# AGG_OBD.net
KiCad netlist of a schematic drawn in EAGLE
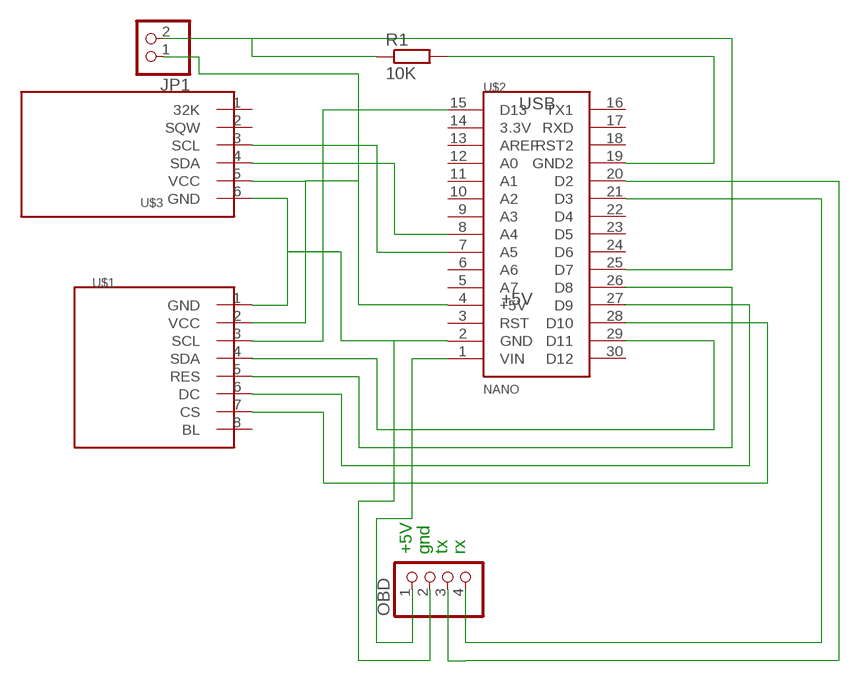
[diagram p0: schematic, sheet 1]

(export (version "E")
  (design (tool "Eeschema 10.0.6"))
  (components
    (comp (ref "JP1")
      (value "PINHD-1X2")
      (footprint "eagle-import:1X02")
      (libsource (lib "eagle-import") (part "PINHD-1X2"))
    )
    (comp (ref "OBD")
      (value "PINHD-1X4")
      (footprint "eagle-import:1X04")
      (libsource (lib "eagle-import") (part "PINHD-1X4"))
    )
    (comp (ref "R1")
      (value "10K")
      (footprint "eagle-import:0207_5V")
      (libsource (lib "eagle-import") (part "R-EU_0207/5V"))
    )
    (comp (ref "U$1")
      (value "DISPLAY_TFT_LCD_128X160")
      (footprint "eagle-import:DISPLAYTFT_LCD128X160")
      (libsource (lib "eagle-import") (part "DISPLAY_TFT_LCD_128X160"))
    )
    (comp (ref "U$2")
      (value "NANO")
      (footprint "eagle-import:NANO")
      (libsource (lib "eagle-import") (part "NANO"))
    )
    (comp (ref "U$3")
      (value "DS3231DS3231")
      (footprint "eagle-import:DS3231")
      (libsource (lib "eagle-import") (part "DS3231DS3231"))
    )
  )
  (nets
    (net (code "1") (name "Net-(U$1-CS)") (class "Default")
      (node (ref "U$1") (pin "7") (pinfunction "CS_7") (pintype "bidirectional"))
      (node (ref "U$2") (pin "28") (pinfunction "D10_28") (pintype "bidirectional"))
    )
    (net (code "2") (name "Net-(U$1-DC)") (class "Default")
      (node (ref "U$1") (pin "6") (pinfunction "DC_6") (pintype "bidirectional"))
      (node (ref "U$2") (pin "27") (pinfunction "D9_27") (pintype "bidirectional"))
    )
    (net (code "3") (name "Net-(U$1-GND)") (class "Default")
      (node (ref "OBD") (pin "2") (pinfunction "2_2") (pintype "passive"))
      (node (ref "U$1") (pin "1") (pinfunction "GND_1") (pintype "bidirectional"))
      (node (ref "U$2") (pin "2") (pinfunction "GND_2") (pintype "bidirectional"))
      (node (ref "U$3") (pin "6") (pinfunction "GND_6") (pintype "bidirectional"))
    )
    (net (code "4") (name "Net-(U$1-RES)") (class "Default")
      (node (ref "U$1") (pin "5") (pinfunction "RES_5") (pintype "bidirectional"))
      (node (ref "U$2") (pin "26") (pinfunction "D8_26") (pintype "bidirectional"))
    )
    (net (code "5") (name "Net-(U$1-SCL)") (class "Default")
      (node (ref "U$1") (pin "3") (pinfunction "SCL_3") (pintype "bidirectional"))
      (node (ref "U$2") (pin "15") (pinfunction "D13_15") (pintype "bidirectional"))
    )
    (net (code "6") (name "Net-(U$1-SDA)") (class "Default")
      (node (ref "U$1") (pin "4") (pinfunction "SDA_4") (pintype "bidirectional"))
      (node (ref "U$2") (pin "29") (pinfunction "D11_29") (pintype "bidirectional"))
    )
    (net (code "7") (name "Net-(U$1-VCC)") (class "Default")
      (node (ref "JP1") (pin "1") (pinfunction "1_1") (pintype "passive"))
      (node (ref "U$1") (pin "2") (pinfunction "VCC_2") (pintype "bidirectional"))
      (node (ref "U$2") (pin "4") (pinfunction "+5V_4") (pintype "bidirectional"))
      (node (ref "U$3") (pin "5") (pinfunction "VCC_5") (pintype "bidirectional"))
    )
    (net (code "8") (name "Net-(U$2-A4)") (class "Default")
      (node (ref "U$2") (pin "8") (pinfunction "A4_8") (pintype "bidirectional"))
      (node (ref "U$3") (pin "4") (pinfunction "SDA_4") (pintype "bidirectional"))
    )
    (net (code "9") (name "Net-(U$2-A5)") (class "Default")
      (node (ref "U$2") (pin "7") (pinfunction "A5_7") (pintype "bidirectional"))
      (node (ref "U$3") (pin "3") (pinfunction "SCL_3") (pintype "bidirectional"))
    )
    (net (code "10") (name "Net-(U$2-D2)") (class "Default")
      (node (ref "OBD") (pin "3") (pinfunction "3_3") (pintype "passive"))
      (node (ref "U$2") (pin "20") (pinfunction "D2_20") (pintype "bidirectional"))
    )
    (net (code "11") (name "Net-(U$2-D3)") (class "Default")
      (node (ref "OBD") (pin "4") (pinfunction "4_4") (pintype "passive"))
      (node (ref "U$2") (pin "21") (pinfunction "D3_21") (pintype "bidirectional"))
    )
    (net (code "12") (name "Net-(U$2-D7)") (class "Default")
      (node (ref "JP1") (pin "2") (pinfunction "2_2") (pintype "passive"))
      (node (ref "R1") (pin "1") (pinfunction "1_1") (pintype "passive"))
      (node (ref "U$2") (pin "25") (pinfunction "D7_25") (pintype "bidirectional"))
    )
    (net (code "13") (name "Net-(U$2-GND2)") (class "Default")
      (node (ref "R1") (pin "2") (pinfunction "2_2") (pintype "passive"))
      (node (ref "U$2") (pin "19") (pinfunction "GND2_19") (pintype "bidirectional"))
    )
    (net (code "14") (name "Net-(U$2-VIN)") (class "Default")
      (node (ref "OBD") (pin "1") (pinfunction "1_1") (pintype "passive"))
      (node (ref "U$2") (pin "1") (pinfunction "VIN_1") (pintype "bidirectional"))
    )
    (net (code "15") (name "unconnected-(U$1-BL-Pad8)") (class "Default")
      (node (ref "U$1") (pin "8") (pinfunction "BL_8") (pintype "bidirectional"))
    )
    (net (code "16") (name "unconnected-(U$2-3.3V-Pad14)") (class "Default")
      (node (ref "U$2") (pin "14") (pinfunction "3.3V_14") (pintype "bidirectional"))
    )
    (net (code "17") (name "unconnected-(U$2-A0-Pad12)") (class "Default")
      (node (ref "U$2") (pin "12") (pinfunction "A0_12") (pintype "bidirectional"))
    )
    (net (code "18") (name "unconnected-(U$2-A1-Pad11)") (class "Default")
      (node (ref "U$2") (pin "11") (pinfunction "A1_11") (pintype "bidirectional"))
    )
    (net (code "19") (name "unconnected-(U$2-A2-Pad10)") (class "Default")
      (node (ref "U$2") (pin "10") (pinfunction "A2_10") (pintype "bidirectional"))
    )
    (net (code "20") (name "unconnected-(U$2-A3-Pad9)") (class "Default")
      (node (ref "U$2") (pin "9") (pinfunction "A3_9") (pintype "bidirectional"))
    )
    (net (code "21") (name "unconnected-(U$2-A6-Pad6)") (class "Default")
      (node (ref "U$2") (pin "6") (pinfunction "A6_6") (pintype "bidirectional"))
    )
    (net (code "22") (name "unconnected-(U$2-A7-Pad5)") (class "Default")
      (node (ref "U$2") (pin "5") (pinfunction "A7_5") (pintype "bidirectional"))
    )
    (net (code "23") (name "unconnected-(U$2-AREF-Pad13)") (class "Default")
      (node (ref "U$2") (pin "13") (pinfunction "AREF_13") (pintype "bidirectional"))
    )
    (net (code "24") (name "unconnected-(U$2-D4-Pad22)") (class "Default")
      (node (ref "U$2") (pin "22") (pinfunction "D4_22") (pintype "bidirectional"))
    )
    (net (code "25") (name "unconnected-(U$2-D5-Pad23)") (class "Default")
      (node (ref "U$2") (pin "23") (pinfunction "D5_23") (pintype "bidirectional"))
    )
    (net (code "26") (name "unconnected-(U$2-D6-Pad24)") (class "Default")
      (node (ref "U$2") (pin "24") (pinfunction "D6_24") (pintype "bidirectional"))
    )
    (net (code "27") (name "unconnected-(U$2-D12-Pad30)") (class "Default")
      (node (ref "U$2") (pin "30") (pinfunction "D12_30") (pintype "bidirectional"))
    )
    (net (code "28") (name "unconnected-(U$2-RST-Pad3)") (class "Default")
      (node (ref "U$2") (pin "3") (pinfunction "RST_3") (pintype "bidirectional"))
    )
    (net (code "29") (name "unconnected-(U$2-RST2-Pad18)") (class "Default")
      (node (ref "U$2") (pin "18") (pinfunction "RST2_18") (pintype "bidirectional"))
    )
    (net (code "30") (name "unconnected-(U$2-RXD-Pad17)") (class "Default")
      (node (ref "U$2") (pin "17") (pinfunction "RXD_17") (pintype "bidirectional"))
    )
    (net (code "31") (name "unconnected-(U$2-TX1-Pad16)") (class "Default")
      (node (ref "U$2") (pin "16") (pinfunction "TX1_16") (pintype "bidirectional"))
    )
    (net (code "32") (name "unconnected-(U$3-32K-Pad1)") (class "Default")
      (node (ref "U$3") (pin "1") (pinfunction "32K_1") (pintype "bidirectional"))
    )
    (net (code "33") (name "unconnected-(U$3-SQW-Pad2)") (class "Default")
      (node (ref "U$3") (pin "2") (pinfunction "SQW_2") (pintype "bidirectional"))
    )
  )
)
